# Pos_Vel_Circuit_Actual.net
KiCad netlist of a schematic drawn in EAGLE
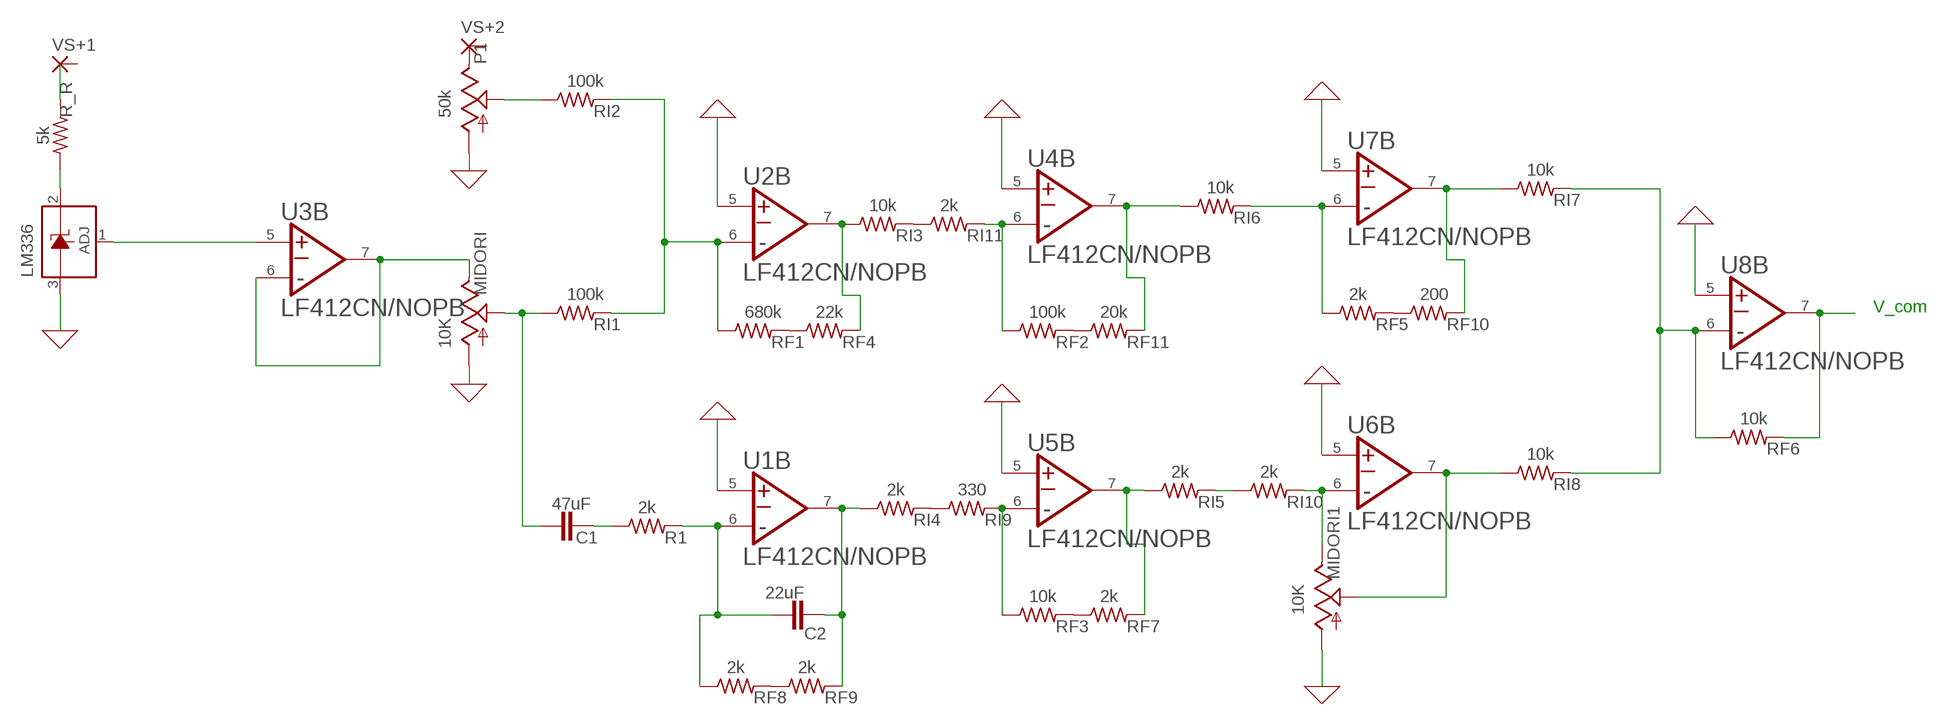
[diagram p0: schematic, sheet 1]

(export (version "E")
  (design (tool "Eeschema 10.0.6"))
  (components
    (comp (ref "C1")
      (value "47uF")
      (footprint "eagle-import:C2.5-3")
      (libsource (lib "eagle-import") (part "C2,5-3"))
    )
    (comp (ref "C2")
      (value "22uF")
      (footprint "eagle-import:C2.5-3")
      (libsource (lib "eagle-import") (part "C2,5-3"))
    )
    (comp (ref "LM336")
      (value "LM336LP")
      (footprint "eagle-import:TO92")
      (libsource (lib "eagle-import") (part "LM336LP"))
    )
    (comp (ref "MIDORI")
      (value "10K")
      (footprint "eagle-import:CIP20C-4MM")
      (libsource (lib "eagle-import") (part "TRIM_US-CIP20C-4MM"))
    )
    (comp (ref "MIDORI1")
      (value "10K")
      (footprint "eagle-import:CIP20C-4MM")
      (libsource (lib "eagle-import") (part "TRIM_US-CIP20C-4MM"))
    )
    (comp (ref "P1")
      (value "50k")
      (footprint "eagle-import:CIP20C-4MM")
      (libsource (lib "eagle-import") (part "TRIM_US-CIP20C-4MM"))
    )
    (comp (ref "R1")
      (value "2k")
      (footprint "eagle-import:0309_10")
      (libsource (lib "eagle-import") (part "R-US_0309/10"))
    )
    (comp (ref "RF1")
      (value "680k")
      (footprint "eagle-import:0309_10")
      (libsource (lib "eagle-import") (part "R-US_0309/10"))
    )
    (comp (ref "RF2")
      (value "100k")
      (footprint "eagle-import:0309_10")
      (libsource (lib "eagle-import") (part "R-US_0309/10"))
    )
    (comp (ref "RF3")
      (value "10k")
      (footprint "eagle-import:0309_10")
      (libsource (lib "eagle-import") (part "R-US_0309/10"))
    )
    (comp (ref "RF4")
      (value "22k")
      (footprint "eagle-import:0309_10")
      (libsource (lib "eagle-import") (part "R-US_0309/10"))
    )
    (comp (ref "RF5")
      (value "2k")
      (footprint "eagle-import:0309_10")
      (libsource (lib "eagle-import") (part "R-US_0309/10"))
    )
    (comp (ref "RF6")
      (value "10k")
      (footprint "eagle-import:0309_10")
      (libsource (lib "eagle-import") (part "R-US_0309/10"))
    )
    (comp (ref "RF7")
      (value "2k")
      (footprint "eagle-import:0309_10")
      (libsource (lib "eagle-import") (part "R-US_0309/10"))
    )
    (comp (ref "RF8")
      (value "2k")
      (footprint "eagle-import:0309_10")
      (libsource (lib "eagle-import") (part "R-US_0309/10"))
    )
    (comp (ref "RF9")
      (value "2k")
      (footprint "eagle-import:0309_10")
      (libsource (lib "eagle-import") (part "R-US_0309/10"))
    )
    (comp (ref "RF10")
      (value "200")
      (footprint "eagle-import:0309_10")
      (libsource (lib "eagle-import") (part "R-US_0309/10"))
    )
    (comp (ref "RF11")
      (value "20k")
      (footprint "eagle-import:0309_10")
      (libsource (lib "eagle-import") (part "R-US_0309/10"))
    )
    (comp (ref "RI1")
      (value "100k")
      (footprint "eagle-import:0309_10")
      (libsource (lib "eagle-import") (part "R-US_0309/10"))
    )
    (comp (ref "RI2")
      (value "100k")
      (footprint "eagle-import:0309_10")
      (libsource (lib "eagle-import") (part "R-US_0309/10"))
    )
    (comp (ref "RI3")
      (value "10k")
      (footprint "eagle-import:0309_10")
      (libsource (lib "eagle-import") (part "R-US_0309/10"))
    )
    (comp (ref "RI4")
      (value "2k")
      (footprint "eagle-import:0309_10")
      (libsource (lib "eagle-import") (part "R-US_0309/10"))
    )
    (comp (ref "RI5")
      (value "2k")
      (footprint "eagle-import:0309_10")
      (libsource (lib "eagle-import") (part "R-US_0309/10"))
    )
    (comp (ref "RI6")
      (value "10k")
      (footprint "eagle-import:0309_10")
      (libsource (lib "eagle-import") (part "R-US_0309/10"))
    )
    (comp (ref "RI7")
      (value "10k")
      (footprint "eagle-import:0309_10")
      (libsource (lib "eagle-import") (part "R-US_0309/10"))
    )
    (comp (ref "RI8")
      (value "10k")
      (footprint "eagle-import:0309_10")
      (libsource (lib "eagle-import") (part "R-US_0309/10"))
    )
    (comp (ref "RI9")
      (value "330")
      (footprint "eagle-import:0309_10")
      (libsource (lib "eagle-import") (part "R-US_0309/10"))
    )
    (comp (ref "RI10")
      (value "2k")
      (footprint "eagle-import:0309_10")
      (libsource (lib "eagle-import") (part "R-US_0309/10"))
    )
    (comp (ref "RI11")
      (value "2k")
      (footprint "eagle-import:0309_10")
      (libsource (lib "eagle-import") (part "R-US_0309/10"))
    )
    (comp (ref "R_R")
      (value "5k")
      (footprint "eagle-import:0309_10")
      (libsource (lib "eagle-import") (part "R-US_0309/10"))
    )
    (comp (ref "U1")
      (value "TEXAS_INSTRUMENTS_LF412CN-NOPBTEXAS_INSTRUMENTS_LF412CN-NOPB_0_0")
      (footprint "eagle-import:TEXAS_INSTRUMENTS_LF412CN-NOPB_0")
      (fields
        (field (name "DIGIKEY_PART_NUMBER") "LF412CN/NOPB-ND")
        (field (name "MF") "Texas Instruments")
        (field (name "MOUSER_PART_NUMBER") "926-LF412CN/NOPB")
      )
      (libsource (lib "eagle-import") (part "TEXAS_INSTRUMENTS_LF412CN-NOPBTEXAS_INSTRUMENTS_LF412CN-NOPB_0_0"))
    )
    (comp (ref "U2")
      (value "TEXAS_INSTRUMENTS_LF412CN-NOPBTEXAS_INSTRUMENTS_LF412CN-NOPB_0_0")
      (footprint "eagle-import:TEXAS_INSTRUMENTS_LF412CN-NOPB_0")
      (fields
        (field (name "DIGIKEY_PART_NUMBER") "LF412CN/NOPB-ND")
        (field (name "MF") "Texas Instruments")
        (field (name "MOUSER_PART_NUMBER") "926-LF412CN/NOPB")
      )
      (libsource (lib "eagle-import") (part "TEXAS_INSTRUMENTS_LF412CN-NOPBTEXAS_INSTRUMENTS_LF412CN-NOPB_0_0"))
    )
    (comp (ref "U3")
      (value "TEXAS_INSTRUMENTS_LF412CN-NOPBTEXAS_INSTRUMENTS_LF412CN-NOPB_0_0")
      (footprint "eagle-import:TEXAS_INSTRUMENTS_LF412CN-NOPB_0")
      (fields
        (field (name "DIGIKEY_PART_NUMBER") "LF412CN/NOPB-ND")
        (field (name "MF") "Texas Instruments")
        (field (name "MOUSER_PART_NUMBER") "926-LF412CN/NOPB")
      )
      (libsource (lib "eagle-import") (part "TEXAS_INSTRUMENTS_LF412CN-NOPBTEXAS_INSTRUMENTS_LF412CN-NOPB_0_0"))
    )
    (comp (ref "U4")
      (value "TEXAS_INSTRUMENTS_LF412CN-NOPBTEXAS_INSTRUMENTS_LF412CN-NOPB_0_0")
      (footprint "eagle-import:TEXAS_INSTRUMENTS_LF412CN-NOPB_0")
      (fields
        (field (name "DIGIKEY_PART_NUMBER") "LF412CN/NOPB-ND")
        (field (name "MF") "Texas Instruments")
        (field (name "MOUSER_PART_NUMBER") "926-LF412CN/NOPB")
      )
      (libsource (lib "eagle-import") (part "TEXAS_INSTRUMENTS_LF412CN-NOPBTEXAS_INSTRUMENTS_LF412CN-NOPB_0_0"))
    )
    (comp (ref "U5")
      (value "TEXAS_INSTRUMENTS_LF412CN-NOPBTEXAS_INSTRUMENTS_LF412CN-NOPB_0_0")
      (footprint "eagle-import:TEXAS_INSTRUMENTS_LF412CN-NOPB_0")
      (fields
        (field (name "DIGIKEY_PART_NUMBER") "LF412CN/NOPB-ND")
        (field (name "MF") "Texas Instruments")
        (field (name "MOUSER_PART_NUMBER") "926-LF412CN/NOPB")
      )
      (libsource (lib "eagle-import") (part "TEXAS_INSTRUMENTS_LF412CN-NOPBTEXAS_INSTRUMENTS_LF412CN-NOPB_0_0"))
    )
    (comp (ref "U6")
      (value "TEXAS_INSTRUMENTS_LF412CN-NOPBTEXAS_INSTRUMENTS_LF412CN-NOPB_0_0")
      (footprint "eagle-import:TEXAS_INSTRUMENTS_LF412CN-NOPB_0")
      (fields
        (field (name "DIGIKEY_PART_NUMBER") "LF412CN/NOPB-ND")
        (field (name "MF") "Texas Instruments")
        (field (name "MOUSER_PART_NUMBER") "926-LF412CN/NOPB")
      )
      (libsource (lib "eagle-import") (part "TEXAS_INSTRUMENTS_LF412CN-NOPBTEXAS_INSTRUMENTS_LF412CN-NOPB_0_0"))
    )
    (comp (ref "U7")
      (value "TEXAS_INSTRUMENTS_LF412CN-NOPBTEXAS_INSTRUMENTS_LF412CN-NOPB_0_0")
      (footprint "eagle-import:TEXAS_INSTRUMENTS_LF412CN-NOPB_0")
      (fields
        (field (name "DIGIKEY_PART_NUMBER") "LF412CN/NOPB-ND")
        (field (name "MF") "Texas Instruments")
        (field (name "MOUSER_PART_NUMBER") "926-LF412CN/NOPB")
      )
      (libsource (lib "eagle-import") (part "TEXAS_INSTRUMENTS_LF412CN-NOPBTEXAS_INSTRUMENTS_LF412CN-NOPB_0_0"))
    )
    (comp (ref "U8")
      (value "TEXAS_INSTRUMENTS_LF412CN-NOPBTEXAS_INSTRUMENTS_LF412CN-NOPB_0_0")
      (footprint "eagle-import:TEXAS_INSTRUMENTS_LF412CN-NOPB_0")
      (fields
        (field (name "DIGIKEY_PART_NUMBER") "LF412CN/NOPB-ND")
        (field (name "MF") "Texas Instruments")
        (field (name "MOUSER_PART_NUMBER") "926-LF412CN/NOPB")
      )
      (libsource (lib "eagle-import") (part "TEXAS_INSTRUMENTS_LF412CN-NOPBTEXAS_INSTRUMENTS_LF412CN-NOPB_0_0"))
    )
    (comp (ref "VS+1")
      (value "1,6/0,8")
      (footprint "eagle-import:1,6_0,8")
      (libsource (lib "eagle-import") (part "1,6/0,8"))
    )
    (comp (ref "VS+2")
      (value "1,6/0,8")
      (footprint "eagle-import:1,6_0,8")
      (libsource (lib "eagle-import") (part "1,6/0,8"))
    )
  )
  (nets
    (net (code "1") (name "GND") (class "Default")
      (node (ref "LM336") (pin "3") (pinfunction "A_3") (pintype "input"))
      (node (ref "MIDORI") (pin "A") (pinfunction "A_A") (pintype "passive"))
      (node (ref "MIDORI1") (pin "A") (pinfunction "A_A") (pintype "passive"))
      (node (ref "P1") (pin "A") (pinfunction "A_A") (pintype "passive"))
      (node (ref "U1") (pin "5") (pinfunction "NON-INVERTING_INPUT_B_5") (pintype "tri_state"))
      (node (ref "U2") (pin "5") (pinfunction "NON-INVERTING_INPUT_B_5") (pintype "tri_state"))
      (node (ref "U4") (pin "5") (pinfunction "NON-INVERTING_INPUT_B_5") (pintype "tri_state"))
      (node (ref "U5") (pin "5") (pinfunction "NON-INVERTING_INPUT_B_5") (pintype "tri_state"))
      (node (ref "U6") (pin "5") (pinfunction "NON-INVERTING_INPUT_B_5") (pintype "tri_state"))
      (node (ref "U7") (pin "5") (pinfunction "NON-INVERTING_INPUT_B_5") (pintype "tri_state"))
      (node (ref "U8") (pin "5") (pinfunction "NON-INVERTING_INPUT_B_5") (pintype "tri_state"))
    )
    (net (code "2") (name "Net-(C1-Pad1)") (class "Default")
      (node (ref "C1") (pin "1") (pinfunction "1_1") (pintype "passive"))
      (node (ref "MIDORI") (pin "S") (pinfunction "S_S") (pintype "passive"))
      (node (ref "RI1") (pin "1") (pinfunction "1_1") (pintype "passive"))
    )
    (net (code "3") (name "Net-(C1-Pad2)") (class "Default")
      (node (ref "C1") (pin "2") (pinfunction "2_2") (pintype "passive"))
      (node (ref "R1") (pin "1") (pinfunction "1_1") (pintype "passive"))
    )
    (net (code "4") (name "Net-(LM336-ADJ)") (class "Default")
      (node (ref "LM336") (pin "1") (pinfunction "ADJ_1") (pintype "input"))
      (node (ref "U3") (pin "5") (pinfunction "NON-INVERTING_INPUT_B_5") (pintype "tri_state"))
    )
    (net (code "5") (name "Net-(LM336-C)") (class "Default")
      (node (ref "LM336") (pin "2") (pinfunction "C_2") (pintype "passive"))
      (node (ref "R_R") (pin "2") (pinfunction "2_2") (pintype "passive"))
    )
    (net (code "6") (name "Net-(P1-PadS)") (class "Default")
      (node (ref "P1") (pin "S") (pinfunction "S_S") (pintype "passive"))
      (node (ref "RI2") (pin "1") (pinfunction "1_1") (pintype "passive"))
    )
    (net (code "7") (name "Net-(RF1-Pad2)") (class "Default")
      (node (ref "RF1") (pin "2") (pinfunction "2_2") (pintype "passive"))
      (node (ref "RF4") (pin "1") (pinfunction "1_1") (pintype "passive"))
    )
    (net (code "8") (name "Net-(RF3-Pad2)") (class "Default")
      (node (ref "RF3") (pin "2") (pinfunction "2_2") (pintype "passive"))
      (node (ref "RF7") (pin "1") (pinfunction "1_1") (pintype "passive"))
    )
    (net (code "9") (name "Net-(RF8-Pad2)") (class "Default")
      (node (ref "RF8") (pin "2") (pinfunction "2_2") (pintype "passive"))
      (node (ref "RF9") (pin "1") (pinfunction "1_1") (pintype "passive"))
    )
    (net (code "10") (name "Net-(RF10-Pad1)") (class "Default")
      (node (ref "RF10") (pin "1") (pinfunction "1_1") (pintype "passive"))
      (node (ref "RF5") (pin "2") (pinfunction "2_2") (pintype "passive"))
    )
    (net (code "11") (name "Net-(RF11-Pad1)") (class "Default")
      (node (ref "RF11") (pin "1") (pinfunction "1_1") (pintype "passive"))
      (node (ref "RF2") (pin "2") (pinfunction "2_2") (pintype "passive"))
    )
    (net (code "12") (name "Net-(RI4-Pad2)") (class "Default")
      (node (ref "RI4") (pin "2") (pinfunction "2_2") (pintype "passive"))
      (node (ref "RI9") (pin "1") (pinfunction "1_1") (pintype "passive"))
    )
    (net (code "13") (name "Net-(RI10-Pad1)") (class "Default")
      (node (ref "RI10") (pin "1") (pinfunction "1_1") (pintype "passive"))
      (node (ref "RI5") (pin "2") (pinfunction "2_2") (pintype "passive"))
    )
    (net (code "14") (name "Net-(RI11-Pad1)") (class "Default")
      (node (ref "RI11") (pin "1") (pinfunction "1_1") (pintype "passive"))
      (node (ref "RI3") (pin "2") (pinfunction "2_2") (pintype "passive"))
    )
    (net (code "15") (name "Net-(U1B-INVERTING_INPUT_B)") (class "Default")
      (node (ref "C2") (pin "1") (pinfunction "1_1") (pintype "passive"))
      (node (ref "R1") (pin "2") (pinfunction "2_2") (pintype "passive"))
      (node (ref "RF8") (pin "1") (pinfunction "1_1") (pintype "passive"))
      (node (ref "U1") (pin "6") (pinfunction "INVERTING_INPUT_B_6") (pintype "tri_state"))
    )
    (net (code "16") (name "Net-(U1B-OUTPUT_B)") (class "Default")
      (node (ref "C2") (pin "2") (pinfunction "2_2") (pintype "passive"))
      (node (ref "RF9") (pin "2") (pinfunction "2_2") (pintype "passive"))
      (node (ref "RI4") (pin "1") (pinfunction "1_1") (pintype "passive"))
      (node (ref "U1") (pin "7") (pinfunction "OUTPUT_B_7") (pintype "passive"))
    )
    (net (code "17") (name "Net-(U2B-INVERTING_INPUT_B)") (class "Default")
      (node (ref "RF1") (pin "1") (pinfunction "1_1") (pintype "passive"))
      (node (ref "RI1") (pin "2") (pinfunction "2_2") (pintype "passive"))
      (node (ref "RI2") (pin "2") (pinfunction "2_2") (pintype "passive"))
      (node (ref "U2") (pin "6") (pinfunction "INVERTING_INPUT_B_6") (pintype "tri_state"))
    )
    (net (code "18") (name "Net-(U2B-OUTPUT_B)") (class "Default")
      (node (ref "RF4") (pin "2") (pinfunction "2_2") (pintype "passive"))
      (node (ref "RI3") (pin "1") (pinfunction "1_1") (pintype "passive"))
      (node (ref "U2") (pin "7") (pinfunction "OUTPUT_B_7") (pintype "passive"))
    )
    (net (code "19") (name "Net-(U3B-INVERTING_INPUT_B)") (class "Default")
      (node (ref "MIDORI") (pin "E") (pinfunction "E_E") (pintype "passive"))
      (node (ref "U3") (pin "6") (pinfunction "INVERTING_INPUT_B_6") (pintype "tri_state"))
      (node (ref "U3") (pin "7") (pinfunction "OUTPUT_B_7") (pintype "passive"))
    )
    (net (code "20") (name "Net-(U4B-INVERTING_INPUT_B)") (class "Default")
      (node (ref "RF2") (pin "1") (pinfunction "1_1") (pintype "passive"))
      (node (ref "RI11") (pin "2") (pinfunction "2_2") (pintype "passive"))
      (node (ref "U4") (pin "6") (pinfunction "INVERTING_INPUT_B_6") (pintype "tri_state"))
    )
    (net (code "21") (name "Net-(U4B-OUTPUT_B)") (class "Default")
      (node (ref "RF11") (pin "2") (pinfunction "2_2") (pintype "passive"))
      (node (ref "RI6") (pin "1") (pinfunction "1_1") (pintype "passive"))
      (node (ref "U4") (pin "7") (pinfunction "OUTPUT_B_7") (pintype "passive"))
    )
    (net (code "22") (name "Net-(U5B-INVERTING_INPUT_B)") (class "Default")
      (node (ref "RF3") (pin "1") (pinfunction "1_1") (pintype "passive"))
      (node (ref "RI9") (pin "2") (pinfunction "2_2") (pintype "passive"))
      (node (ref "U5") (pin "6") (pinfunction "INVERTING_INPUT_B_6") (pintype "tri_state"))
    )
    (net (code "23") (name "Net-(U5B-OUTPUT_B)") (class "Default")
      (node (ref "RF7") (pin "2") (pinfunction "2_2") (pintype "passive"))
      (node (ref "RI5") (pin "1") (pinfunction "1_1") (pintype "passive"))
      (node (ref "U5") (pin "7") (pinfunction "OUTPUT_B_7") (pintype "passive"))
    )
    (net (code "24") (name "Net-(U6B-INVERTING_INPUT_B)") (class "Default")
      (node (ref "MIDORI1") (pin "E") (pinfunction "E_E") (pintype "passive"))
      (node (ref "RI10") (pin "2") (pinfunction "2_2") (pintype "passive"))
      (node (ref "U6") (pin "6") (pinfunction "INVERTING_INPUT_B_6") (pintype "tri_state"))
    )
    (net (code "25") (name "Net-(U6B-OUTPUT_B)") (class "Default")
      (node (ref "MIDORI1") (pin "S") (pinfunction "S_S") (pintype "passive"))
      (node (ref "RI8") (pin "1") (pinfunction "1_1") (pintype "passive"))
      (node (ref "U6") (pin "7") (pinfunction "OUTPUT_B_7") (pintype "passive"))
    )
    (net (code "26") (name "Net-(U7B-INVERTING_INPUT_B)") (class "Default")
      (node (ref "RF5") (pin "1") (pinfunction "1_1") (pintype "passive"))
      (node (ref "RI6") (pin "2") (pinfunction "2_2") (pintype "passive"))
      (node (ref "U7") (pin "6") (pinfunction "INVERTING_INPUT_B_6") (pintype "tri_state"))
    )
    (net (code "27") (name "Net-(U7B-OUTPUT_B)") (class "Default")
      (node (ref "RF10") (pin "2") (pinfunction "2_2") (pintype "passive"))
      (node (ref "RI7") (pin "1") (pinfunction "1_1") (pintype "passive"))
      (node (ref "U7") (pin "7") (pinfunction "OUTPUT_B_7") (pintype "passive"))
    )
    (net (code "28") (name "Net-(U8B-INVERTING_INPUT_B)") (class "Default")
      (node (ref "RF6") (pin "1") (pinfunction "1_1") (pintype "passive"))
      (node (ref "RI7") (pin "2") (pinfunction "2_2") (pintype "passive"))
      (node (ref "RI8") (pin "2") (pinfunction "2_2") (pintype "passive"))
      (node (ref "U8") (pin "6") (pinfunction "INVERTING_INPUT_B_6") (pintype "tri_state"))
    )
    (net (code "29") (name "Net-(U8B-OUTPUT_B)") (class "Default")
      (node (ref "RF6") (pin "2") (pinfunction "2_2") (pintype "passive"))
      (node (ref "U8") (pin "7") (pinfunction "OUTPUT_B_7") (pintype "passive"))
    )
    (net (code "30") (name "unconnected-(P1-PadE)") (class "Default")
      (node (ref "P1") (pin "E") (pinfunction "E_E") (pintype "passive"))
    )
    (net (code "31") (name "unconnected-(R_R-Pad1)") (class "Default")
      (node (ref "R_R") (pin "1") (pinfunction "1_1") (pintype "passive"))
    )
    (net (code "32") (name "unconnected-(VS+1-P-Pad1)") (class "Default")
      (node (ref "VS+1") (pin "1") (pinfunction "P_1") (pintype "passive"))
    )
    (net (code "33") (name "unconnected-(VS+2-P-Pad1)") (class "Default")
      (node (ref "VS+2") (pin "1") (pinfunction "P_1") (pintype "passive"))
    )
  )
)
